# Led.net
KiCad netlist of a schematic drawn in Altium Designer
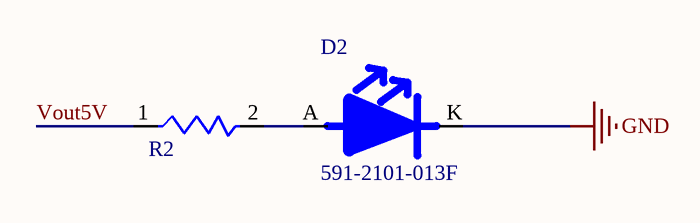
[diagram p0: Led.SchDoc]

(export (version "E")
  (design (tool "Eeschema 10.0.6"))
  (components
    (comp (ref "D2")
      (value "591-2101-013F")
      (footprint "LED5MM")
      (fields (field (name "MANUFACTURER") "Dialight"))
      (libsource (lib "EgitimPowerSupply") (part "591-2101-013F"))
    )
    (comp (ref "R2")
      (value "Res")
      (footprint "R1")
      (description "RES 10K OHM 1/4W 5% CARBON FILM")
      (fields
        (field (name "MANUFACTURER") "Stackpole Electronics Inc")
        (field (name "MANUFACTURER PART NUMBER") "CF14JT10K0")
      )
      (libsource (lib "EgitimPowerSupply") (part "CF14JT10K0"))
    )
  )
  (nets
    (net (code "1") (name "/Vout5V") (class "Default")
      (node (ref "R2") (pin "1") (pinfunction "1_1") (pintype "passive"))
    )
    (net (code "2") (name "GND") (class "Default")
      (node (ref "D2") (pin "K") (pinfunction "K_K") (pintype "passive"))
    )
    (net (code "3") (name "Net-(D2-PadA)") (class "Default")
      (node (ref "D2") (pin "A") (pinfunction "A_A") (pintype "passive"))
      (node (ref "R2") (pin "2") (pinfunction "2_2") (pintype "passive"))
    )
  )
)
